# Power.net
KiCad netlist of a schematic drawn in Altium Designer
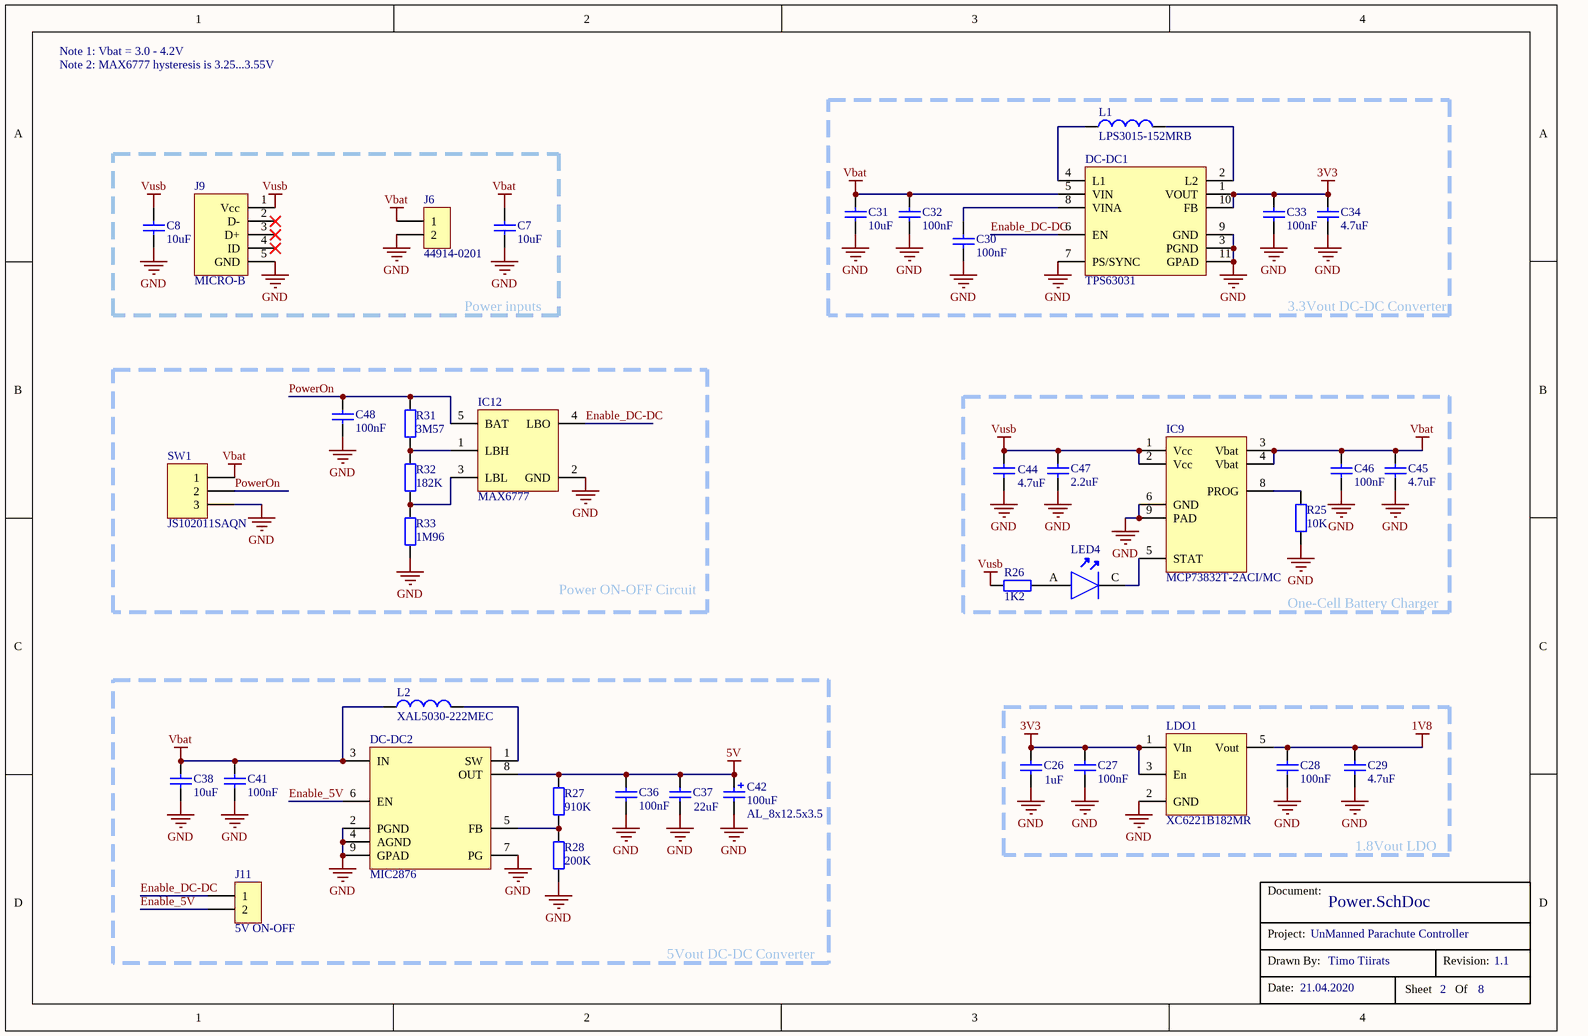
[diagram p0: Power.SchDoc]

(export (version "E")
  (design (tool "Eeschema 10.0.6"))
  (components
    (comp (ref "C7")
      (value "10uF*V")
      (footprint "C1206 N")
      (description "Ceramic capacitor")
      (fields (field (name "CAPACITANCE") "10uF"))
      (libsource (lib "Passives") (part "Capacitor"))
    )
    (comp (ref "C8")
      (value "10uF*V")
      (footprint "C1206 N")
      (description "Ceramic capacitor")
      (fields (field (name "CAPACITANCE") "10uF"))
      (libsource (lib "Passives") (part "Capacitor"))
    )
    (comp (ref "C26")
      (value "1uF*V")
      (footprint "C0603 N")
      (description "Ceramic capacitor")
      (fields (field (name "CAPACITANCE") "1uF"))
      (libsource (lib "Passives") (part "Capacitor"))
    )
    (comp (ref "C27")
      (value "100nF*V")
      (footprint "C0603 N")
      (description "Ceramic capacitor")
      (fields (field (name "CAPACITANCE") "100nF"))
      (libsource (lib "Passives") (part "Capacitor"))
    )
    (comp (ref "C28")
      (value "100nF*V")
      (footprint "C0603 N")
      (description "Ceramic capacitor")
      (fields (field (name "CAPACITANCE") "100nF"))
      (libsource (lib "Passives") (part "Capacitor"))
    )
    (comp (ref "C29")
      (value "4.7uF*V")
      (footprint "C0603 N")
      (description "Ceramic capacitor")
      (fields (field (name "CAPACITANCE") "4.7uF"))
      (libsource (lib "Passives") (part "Capacitor"))
    )
    (comp (ref "C30")
      (value "100nF*V")
      (footprint "C0603 N")
      (description "Ceramic capacitor")
      (fields (field (name "CAPACITANCE") "100nF"))
      (libsource (lib "Passives") (part "Capacitor"))
    )
    (comp (ref "C31")
      (value "10uF*V")
      (footprint "C1206 N")
      (description "Ceramic capacitor")
      (fields (field (name "CAPACITANCE") "10uF"))
      (libsource (lib "Passives") (part "Capacitor"))
    )
    (comp (ref "C32")
      (value "100nF*V")
      (footprint "C0603 N")
      (description "Ceramic capacitor")
      (fields (field (name "CAPACITANCE") "100nF"))
      (libsource (lib "Passives") (part "Capacitor"))
    )
    (comp (ref "C33")
      (value "100nF*V")
      (footprint "C0603 N")
      (description "Ceramic capacitor")
      (fields (field (name "CAPACITANCE") "100nF"))
      (libsource (lib "Passives") (part "Capacitor"))
    )
    (comp (ref "C34")
      (value "4.7uF*V")
      (footprint "C0603 N")
      (description "Ceramic capacitor")
      (fields (field (name "CAPACITANCE") "4.7uF"))
      (libsource (lib "Passives") (part "Capacitor"))
    )
    (comp (ref "C36")
      (value "100nF*V")
      (footprint "C0603 N")
      (description "Ceramic capacitor")
      (fields (field (name "CAPACITANCE") "100nF"))
      (libsource (lib "Passives") (part "Capacitor"))
    )
    (comp (ref "C37")
      (value "22uF*V")
      (footprint "C1206 N")
      (description "Ceramic capacitor")
      (fields (field (name "CAPACITANCE") "22uF"))
      (libsource (lib "Passives") (part "Capacitor"))
    )
    (comp (ref "C38")
      (value "10uF*V")
      (footprint "C1206 N")
      (description "Ceramic capacitor")
      (fields (field (name "CAPACITANCE") "10uF"))
      (libsource (lib "Passives") (part "Capacitor"))
    )
    (comp (ref "C41")
      (value "100nF*V")
      (footprint "C0603 N")
      (description "Ceramic capacitor")
      (fields (field (name "CAPACITANCE") "100nF"))
      (libsource (lib "Passives") (part "Capacitor"))
    )
    (comp (ref "C42")
      (value "100uF*V")
      (footprint "AL_8x12.5x3.5")
      (description "Polarized Capacitor")
      (fields (field (name "CAPACITANCE") "100uF"))
      (libsource (lib "Passives") (part "Capacitor Polarized"))
    )
    (comp (ref "C44")
      (value "4.7uF*V")
      (footprint "C1206 N")
      (description "Ceramic capacitor")
      (fields (field (name "CAPACITANCE") "4.7uF"))
      (libsource (lib "Passives") (part "Capacitor"))
    )
    (comp (ref "C45")
      (value "4.7uF*V")
      (footprint "C1206 N")
      (description "Ceramic capacitor")
      (fields (field (name "CAPACITANCE") "4.7uF"))
      (libsource (lib "Passives") (part "Capacitor"))
    )
    (comp (ref "C46")
      (value "100nF*V")
      (footprint "C0603 N")
      (description "Ceramic capacitor")
      (fields (field (name "CAPACITANCE") "100nF"))
      (libsource (lib "Passives") (part "Capacitor"))
    )
    (comp (ref "C47")
      (value "2.2uF*V")
      (footprint "C0603 N")
      (description "Ceramic capacitor")
      (fields (field (name "CAPACITANCE") "2.2uF"))
      (libsource (lib "Passives") (part "Capacitor"))
    )
    (comp (ref "C48")
      (value "100nF*V")
      (footprint "C0603 N")
      (description "Ceramic capacitor")
      (fields (field (name "CAPACITANCE") "100nF"))
      (libsource (lib "Passives") (part "Capacitor"))
    )
    (comp (ref "DC-DC1")
      (value "TPS63031")
      (footprint "WSON10, 2.6x2.6, LEAST")
      (description "DC-DC CONVERTER, 3.3Vout, 1.8...5.5Vin, buck-boost, 800mA, TPS63031, TEXAS INSTRUMENTS")
      (libsource (lib "DC-DC") (part "TPS63031"))
    )
    (comp (ref "DC-DC2")
      (value "MIC2876")
      (footprint "QFN-8 2x2MM, NOMINAL")
      (description "DC-DC CONVERTER, ADJ, Vin...5.5Vout, 2.5...5.5Vin, 4.8A, boost, MIC2875, Microchip")
      (libsource (lib "DC-DC") (part "MIC2876"))
    )
    (comp (ref "IC9")
      (value "MCP73832T-2ACI/MC")
      (footprint "DFN-8, 2X3MM")
      (fields (field (name "MANUFACTURER") "Microchip"))
      (libsource (lib "BatteryManagement") (part "MCP73832T-2ACI"))
    )
    (comp (ref "IC12")
      (value "MAX6777")
      (footprint "SOT323-5, Nominal")
      (description "Battery monitor, 1 cell, Li-ion, adj hysteresis, 1.0...5.5Vin, MAX6777, Maxim")
      (libsource (lib "BatteryManagement") (part "MAX6777"))
    )
    (comp (ref "J6")
      (value "44914-0201")
      (footprint "44914-0201")
      (description "MicroFit 2-pin CPI Header, 2 Row, Vertical")
      (fields (field (name "MANUFACTURER") "Molex"))
      (libsource (lib "MicroFit") (part "44914-0201"))
    )
    (comp (ref "J9")
      (value "MICRO-B")
      (footprint "MICRO-B")
      (description "Micro USB 2.0 type B, receptacle")
      (fields (field (name "MANUFACTURER") "Molex") (field (name "MANUFACTURER PART NUMBER") "47346-1001"))
      (libsource (lib "USB") (part "MICRO-B"))
    )
    (comp (ref "J11")
      (value "5V ON-OFF")
      (footprint "Male 1x2 vertical")
      (libsource (lib "pinheader") (part "header 1x2 vertical"))
    )
    (comp (ref "L1")
      (value "LPS3015-152MRB")
      (footprint "LPS3010")
      (description "Inductor, 1.5uH, 100mR, 1.3A, LPS3015-152MRB, COILCRAFT")
      (libsource (lib "Inductors") (part "LPS3015-152MRB"))
    )
    (comp (ref "L2")
      (value "XAL5030-222MEC")
      (footprint "XAL5030-222MEC")
      (description "Inductor, 2.2uH, 14mR, 9.2A, Coilcraft, XAL5030-222MEC")
      (libsource (lib "Inductors") (part "XAL5030-222MEC"))
    )
    (comp (ref "LDO1")
      (value "XC6221B182MR")
      (footprint "SOT-23-5, Nominal")
      (description "LDO, 1.8Vout, 1.6-6Vin, SOT-25, SMD,  HIGH SPEED LOW NOISE, TOREX - XC6221B182MR")
      (fields (field (name "MANUFACTURER") "TOREX"))
      (libsource (lib "LDO") (part "XC6221B182MR"))
    )
    (comp (ref "LED4")
      (value "DebugLED1")
      (footprint "0603 NOMINAL")
      (description "SMD mono-color Chip LED")
      (libsource (lib "LEDs") (part "Generic LED"))
    )
    (comp (ref "R25")
      (value "10K")
      (footprint "R0603")
      (description "Resistor")
      (fields (field (name "RESISTANCE") "10K"))
      (libsource (lib "Passives") (part "Resistor"))
    )
    (comp (ref "R26")
      (value "1K2")
      (footprint "R0603")
      (description "Resistor")
      (fields (field (name "RESISTANCE") "1K2"))
      (libsource (lib "") (part "Resistor_1"))
    )
    (comp (ref "R27")
      (value "910K")
      (footprint "R0603")
      (description "Resistor")
      (fields (field (name "RESISTANCE") "910K"))
      (libsource (lib "") (part "Resistor_2"))
    )
    (comp (ref "R28")
      (value "200K")
      (footprint "R0603")
      (description "Resistor")
      (fields (field (name "RESISTANCE") "200K"))
      (libsource (lib "") (part "Resistor_2"))
    )
    (comp (ref "R31")
      (value "3M57")
      (footprint "R0603")
      (description "Resistor")
      (fields (field (name "RESISTANCE") "3M57"))
      (libsource (lib "Passives") (part "Resistor"))
    )
    (comp (ref "R32")
      (value "182K")
      (footprint "R0603")
      (description "Resistor")
      (fields (field (name "RESISTANCE") "182K"))
      (libsource (lib "Passives") (part "Resistor"))
    )
    (comp (ref "R33")
      (value "1M96")
      (footprint "R0603")
      (description "Resistor")
      (fields (field (name "RESISTANCE") "1M96"))
      (libsource (lib "Passives") (part "Resistor"))
    )
    (comp (ref "SW1")
      (value "JS102011SAQN")
      (footprint "JS102011SAQN")
      (fields (field (name "MANUFACTURER") "ITT C&K"))
      (libsource (lib "Switches") (part "JS102011SAQN"))
    )
  )
  (nets
    (net (code "1") (name "/Enable_5V") (class "Default")
      (node (ref "DC-DC2") (pin "6") (pinfunction "EN_6") (pintype "passive"))
      (node (ref "J11") (pin "2") (pinfunction "2_2") (pintype "passive"))
    )
    (net (code "2") (name "/Enable_DC-DC") (class "Default")
      (node (ref "DC-DC1") (pin "6") (pinfunction "EN_6") (pintype "passive"))
      (node (ref "IC12") (pin "4") (pinfunction "LBO_4") (pintype "passive"))
      (node (ref "J11") (pin "1") (pinfunction "1_1") (pintype "passive"))
    )
    (net (code "3") (name "/PowerOn") (class "Default")
      (node (ref "C48") (pin "2") (pinfunction "2_2") (pintype "passive"))
      (node (ref "IC12") (pin "5") (pinfunction "BAT_5") (pintype "passive"))
      (node (ref "R31") (pin "1") (pinfunction "1_1") (pintype "passive"))
      (node (ref "SW1") (pin "2") (pinfunction "2_2") (pintype "passive"))
    )
    (net (code "4") (name "1V8") (class "Default")
      (node (ref "C28") (pin "2") (pinfunction "2_2") (pintype "passive"))
      (node (ref "C29") (pin "2") (pinfunction "2_2") (pintype "passive"))
      (node (ref "LDO1") (pin "5") (pinfunction "Vout_5") (pintype "passive"))
    )
    (net (code "5") (name "3V3") (class "Default")
      (node (ref "C26") (pin "2") (pinfunction "2_2") (pintype "passive"))
      (node (ref "C27") (pin "2") (pinfunction "2_2") (pintype "passive"))
      (node (ref "C33") (pin "2") (pinfunction "2_2") (pintype "passive"))
      (node (ref "C34") (pin "2") (pinfunction "2_2") (pintype "passive"))
      (node (ref "DC-DC1") (pin "1") (pinfunction "VOUT_1") (pintype "passive"))
      (node (ref "DC-DC1") (pin "10") (pinfunction "FB_10") (pintype "passive"))
      (node (ref "LDO1") (pin "1") (pinfunction "VIn_1") (pintype "passive"))
      (node (ref "LDO1") (pin "3") (pinfunction "En_3") (pintype "passive"))
    )
    (net (code "6") (name "5V") (class "Default")
      (node (ref "C36") (pin "2") (pinfunction "2_2") (pintype "passive"))
      (node (ref "C37") (pin "2") (pinfunction "2_2") (pintype "passive"))
      (node (ref "C42") (pin "1") (pinfunction "1_1") (pintype "passive"))
      (node (ref "DC-DC2") (pin "8") (pinfunction "OUT_8") (pintype "passive"))
      (node (ref "R27") (pin "2") (pinfunction "2_2") (pintype "passive"))
    )
    (net (code "7") (name "GND") (class "Default")
      (node (ref "C26") (pin "1") (pinfunction "1_1") (pintype "passive"))
      (node (ref "C27") (pin "1") (pinfunction "1_1") (pintype "passive"))
      (node (ref "C28") (pin "1") (pinfunction "1_1") (pintype "passive"))
      (node (ref "C29") (pin "1") (pinfunction "1_1") (pintype "passive"))
      (node (ref "C30") (pin "1") (pinfunction "1_1") (pintype "passive"))
      (node (ref "C31") (pin "1") (pinfunction "1_1") (pintype "passive"))
      (node (ref "C32") (pin "1") (pinfunction "1_1") (pintype "passive"))
      (node (ref "C33") (pin "1") (pinfunction "1_1") (pintype "passive"))
      (node (ref "C34") (pin "1") (pinfunction "1_1") (pintype "passive"))
      (node (ref "C36") (pin "1") (pinfunction "1_1") (pintype "passive"))
      (node (ref "C37") (pin "1") (pinfunction "1_1") (pintype "passive"))
      (node (ref "C38") (pin "1") (pinfunction "1_1") (pintype "passive"))
      (node (ref "C41") (pin "1") (pinfunction "1_1") (pintype "passive"))
      (node (ref "C42") (pin "2") (pinfunction "2_2") (pintype "passive"))
      (node (ref "C44") (pin "1") (pinfunction "1_1") (pintype "passive"))
      (node (ref "C45") (pin "1") (pinfunction "1_1") (pintype "passive"))
      (node (ref "C46") (pin "1") (pinfunction "1_1") (pintype "passive"))
      (node (ref "C47") (pin "1") (pinfunction "1_1") (pintype "passive"))
      (node (ref "C48") (pin "1") (pinfunction "1_1") (pintype "passive"))
      (node (ref "C7") (pin "1") (pinfunction "1_1") (pintype "passive"))
      (node (ref "C8") (pin "1") (pinfunction "1_1") (pintype "passive"))
      (node (ref "DC-DC1") (pin "11") (pinfunction "GPAD_11") (pintype "passive"))
      (node (ref "DC-DC1") (pin "3") (pinfunction "PGND_3") (pintype "passive"))
      (node (ref "DC-DC1") (pin "7") (pinfunction "PS/SYNC_7") (pintype "passive"))
      (node (ref "DC-DC1") (pin "9") (pinfunction "GND_9") (pintype "passive"))
      (node (ref "DC-DC2") (pin "2") (pinfunction "PGND_2") (pintype "passive"))
      (node (ref "DC-DC2") (pin "4") (pinfunction "AGND_4") (pintype "passive"))
      (node (ref "DC-DC2") (pin "7") (pinfunction "PG_7") (pintype "passive"))
      (node (ref "DC-DC2") (pin "9") (pinfunction "GPAD_9") (pintype "passive"))
      (node (ref "IC12") (pin "2") (pinfunction "GND_2") (pintype "passive"))
      (node (ref "IC9") (pin "6") (pinfunction "GND_6") (pintype "passive"))
      (node (ref "IC9") (pin "9") (pinfunction "PAD_9") (pintype "passive"))
      (node (ref "J6") (pin "2") (pinfunction "2_2") (pintype "passive"))
      (node (ref "J9") (pin "5") (pinfunction "GND_5") (pintype "passive"))
      (node (ref "LDO1") (pin "2") (pinfunction "GND_2") (pintype "passive"))
      (node (ref "R25") (pin "2") (pinfunction "2_2") (pintype "passive"))
      (node (ref "R28") (pin "1") (pinfunction "1_1") (pintype "passive"))
      (node (ref "R33") (pin "2") (pinfunction "2_2") (pintype "passive"))
      (node (ref "SW1") (pin "3") (pinfunction "3_3") (pintype "passive"))
    )
    (net (code "8") (name "Net-(DC-DC1-L1)") (class "Default")
      (node (ref "DC-DC1") (pin "4") (pinfunction "L1_4") (pintype "passive"))
      (node (ref "L1") (pin "1") (pinfunction "1_1") (pintype "passive"))
    )
    (net (code "9") (name "Net-(DC-DC1-L2)") (class "Default")
      (node (ref "DC-DC1") (pin "2") (pinfunction "L2_2") (pintype "passive"))
      (node (ref "L1") (pin "2") (pinfunction "2_2") (pintype "passive"))
    )
    (net (code "10") (name "Net-(DC-DC1-VINA)") (class "Default")
      (node (ref "C30") (pin "2") (pinfunction "2_2") (pintype "passive"))
      (node (ref "DC-DC1") (pin "8") (pinfunction "VINA_8") (pintype "passive"))
    )
    (net (code "11") (name "Net-(DC-DC2-FB)") (class "Default")
      (node (ref "DC-DC2") (pin "5") (pinfunction "FB_5") (pintype "passive"))
      (node (ref "R27") (pin "1") (pinfunction "1_1") (pintype "passive"))
      (node (ref "R28") (pin "2") (pinfunction "2_2") (pintype "passive"))
    )
    (net (code "12") (name "Net-(DC-DC2-SW)") (class "Default")
      (node (ref "DC-DC2") (pin "1") (pinfunction "SW_1") (pintype "passive"))
      (node (ref "L2") (pin "2") (pinfunction "2_2") (pintype "passive"))
    )
    (net (code "13") (name "Net-(IC9-PROG)") (class "Default")
      (node (ref "IC9") (pin "8") (pinfunction "PROG_8") (pintype "passive"))
      (node (ref "R25") (pin "1") (pinfunction "1_1") (pintype "passive"))
    )
    (net (code "14") (name "Net-(IC9-STAT)") (class "Default")
      (node (ref "IC9") (pin "5") (pinfunction "STAT_5") (pintype "passive"))
      (node (ref "LED4") (pin "C") (pinfunction "C_C") (pintype "passive"))
    )
    (net (code "15") (name "Net-(IC12-LBH)") (class "Default")
      (node (ref "IC12") (pin "1") (pinfunction "LBH_1") (pintype "passive"))
      (node (ref "R31") (pin "2") (pinfunction "2_2") (pintype "passive"))
      (node (ref "R32") (pin "1") (pinfunction "1_1") (pintype "passive"))
    )
    (net (code "16") (name "Net-(IC12-LBL)") (class "Default")
      (node (ref "IC12") (pin "3") (pinfunction "LBL_3") (pintype "passive"))
      (node (ref "R32") (pin "2") (pinfunction "2_2") (pintype "passive"))
      (node (ref "R33") (pin "1") (pinfunction "1_1") (pintype "passive"))
    )
    (net (code "17") (name "Net-(LED4-PadA)") (class "Default")
      (node (ref "LED4") (pin "A") (pinfunction "A_A") (pintype "passive"))
      (node (ref "R26") (pin "2") (pinfunction "2_2") (pintype "passive"))
    )
    (net (code "18") (name "Vbat") (class "Default")
      (node (ref "C31") (pin "2") (pinfunction "2_2") (pintype "passive"))
      (node (ref "C32") (pin "2") (pinfunction "2_2") (pintype "passive"))
      (node (ref "C38") (pin "2") (pinfunction "2_2") (pintype "passive"))
      (node (ref "C41") (pin "2") (pinfunction "2_2") (pintype "passive"))
      (node (ref "C45") (pin "2") (pinfunction "2_2") (pintype "passive"))
      (node (ref "C46") (pin "2") (pinfunction "2_2") (pintype "passive"))
      (node (ref "C7") (pin "2") (pinfunction "2_2") (pintype "passive"))
      (node (ref "DC-DC1") (pin "5") (pinfunction "VIN_5") (pintype "passive"))
      (node (ref "DC-DC2") (pin "3") (pinfunction "IN_3") (pintype "passive"))
      (node (ref "IC9") (pin "3") (pinfunction "Vbat_3") (pintype "passive"))
      (node (ref "IC9") (pin "4") (pinfunction "Vbat_4") (pintype "passive"))
      (node (ref "J6") (pin "1") (pinfunction "1_1") (pintype "passive"))
      (node (ref "L2") (pin "1") (pinfunction "1_1") (pintype "passive"))
      (node (ref "SW1") (pin "1") (pinfunction "1_1") (pintype "passive"))
    )
    (net (code "19") (name "Vusb") (class "Default")
      (node (ref "C44") (pin "2") (pinfunction "2_2") (pintype "passive"))
      (node (ref "C47") (pin "2") (pinfunction "2_2") (pintype "passive"))
      (node (ref "C8") (pin "2") (pinfunction "2_2") (pintype "passive"))
      (node (ref "IC9") (pin "1") (pinfunction "Vcc_1") (pintype "passive"))
      (node (ref "IC9") (pin "2") (pinfunction "Vcc_2") (pintype "passive"))
      (node (ref "J9") (pin "1") (pinfunction "Vcc_1") (pintype "passive"))
      (node (ref "R26") (pin "1") (pinfunction "1_1") (pintype "passive"))
    )
    (net (code "20") (name "unconnected-(J9-D+-Pad3)") (class "Default")
      (node (ref "J9") (pin "3") (pinfunction "D+_3") (pintype "passive+no_connect"))
    )
    (net (code "21") (name "unconnected-(J9-D--Pad2)") (class "Default")
      (node (ref "J9") (pin "2") (pinfunction "D-_2") (pintype "passive+no_connect"))
    )
    (net (code "22") (name "unconnected-(J9-ID-Pad4)") (class "Default")
      (node (ref "J9") (pin "4") (pinfunction "ID_4") (pintype "passive+no_connect"))
    )
  )
)
